# mightyFan.net
KiCad netlist of a schematic drawn in Altium Designer
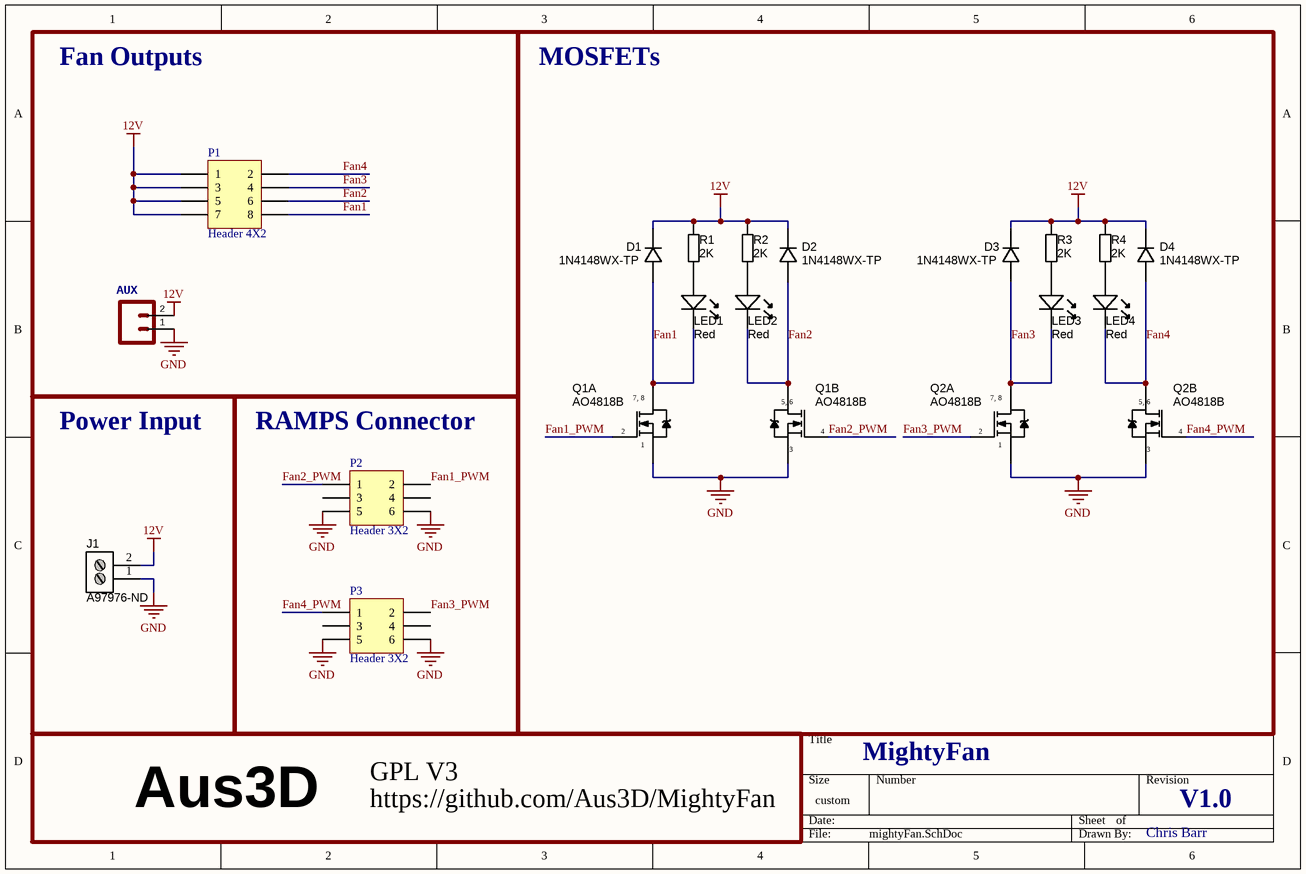
[diagram p0: mightyFan.SchDoc]

(export (version "E")
  (design (tool "Eeschema 10.0.6"))
  (components
    (comp (ref "AUX")
      (value "Standard 2-pin 0.1\" header. Use with  - straight break away headers ( PRT-00116) - right angle break away headers (PRT-00553) - swiss pins (PRT-00743) - machine pins (PRT-00117) - female headers (PRT-00115)   Molex polarized connector foot print use with: PRT-08233 with associated crimp pins and housings.  2.54_SCREWTERM for use with  PRT-10571.  3.5mm Screw Terminal footprints for  PRT-08084  5mm Screw Terminal footprints for use with PRT-08432")
      (footprint "1X02")
      (libsource (lib "SparkFun-Connectors") (part "M02PTH"))
    )
    (comp (ref "D1")
      (value "DIODE_75V_500mW")
      (footprint "SOD323")
      (description "Diode SMD 300mA 0.5W SOD323")
      (fields
        (field (name "MANUFACTURER") "Micro Commercial Co")
        (field (name "MANUFACTURER PART NUMBER") "1N4148WX-TP")
      )
      (libsource (lib "PBL - Diodes") (part "DIODE_75V_500mW"))
    )
    (comp (ref "D2")
      (value "DIODE_75V_500mW")
      (footprint "SOD323")
      (description "Diode SMD 300mA 0.5W SOD323")
      (fields
        (field (name "MANUFACTURER") "Micro Commercial Co")
        (field (name "MANUFACTURER PART NUMBER") "1N4148WX-TP")
      )
      (libsource (lib "PBL - Diodes") (part "DIODE_75V_500mW"))
    )
    (comp (ref "D3")
      (value "DIODE_75V_500mW")
      (footprint "SOD323")
      (description "Diode SMD 300mA 0.5W SOD323")
      (fields
        (field (name "MANUFACTURER") "Micro Commercial Co")
        (field (name "MANUFACTURER PART NUMBER") "1N4148WX-TP")
      )
      (libsource (lib "PBL - Diodes") (part "DIODE_75V_500mW"))
    )
    (comp (ref "D4")
      (value "DIODE_75V_500mW")
      (footprint "SOD323")
      (description "Diode SMD 300mA 0.5W SOD323")
      (fields
        (field (name "MANUFACTURER") "Micro Commercial Co")
        (field (name "MANUFACTURER PART NUMBER") "1N4148WX-TP")
      )
      (libsource (lib "PBL - Diodes") (part "DIODE_75V_500mW"))
    )
    (comp (ref "J1")
      (value "Stackable ScrewTerm")
      (footprint "2P_PCB_ScrewTerm_90S_3.81MM")
      (description "Terminal Block Screw Type THT 2-Position 3.81mm pitch")
      (fields (field (name "SUPPLIER PART NUMBER 1") "A97976-ND"))
      (libsource (lib "PBL - Connectors") (part "2P_ScrewTerm_90S_3.81MM"))
    )
    (comp (ref "LED1")
      (value "Red")
      (footprint "LED-0603-RED")
      (description "LED 0603 SMD Hyper Red 630nm 220mcd 20mA")
      (libsource (lib "PBL - Light Sources") (part "LED_SMD_Red_0603_220mcd"))
    )
    (comp (ref "LED2")
      (value "Red")
      (footprint "LED-0603-RED")
      (description "LED 0603 SMD Hyper Red 630nm 220mcd 20mA")
      (libsource (lib "PBL - Light Sources") (part "LED_SMD_Red_0603_220mcd"))
    )
    (comp (ref "LED3")
      (value "Red")
      (footprint "LED-0603-RED")
      (description "LED 0603 SMD Hyper Red 630nm 220mcd 20mA")
      (libsource (lib "PBL - Light Sources") (part "LED_SMD_Red_0603_220mcd"))
    )
    (comp (ref "LED4")
      (value "Red")
      (footprint "LED-0603-RED")
      (description "LED 0603 SMD Hyper Red 630nm 220mcd 20mA")
      (libsource (lib "PBL - Light Sources") (part "LED_SMD_Red_0603_220mcd"))
    )
    (comp (ref "P1")
      (value "Header 4X2")
      (footprint "2X4")
      (description "Header, 4-Pin, Dual row")
      (fields (field (name "PUBLISHER") "Altium Limited"))
      (libsource (lib "Miscellaneous Connectors") (part "Header 4X2"))
    )
    (comp (ref "P2")
      (value "Header 3X2")
      (footprint "Header-3x2-female")
      (description "Header, 3-Pin, Dual row")
      (fields (field (name "PUBLISHER") "Altium Limited"))
      (libsource (lib "Miscellaneous Connectors") (part "Header 3X2"))
    )
    (comp (ref "P3")
      (value "Header 3X2")
      (footprint "Header-3x2-female")
      (description "Header, 3-Pin, Dual row")
      (fields (field (name "PUBLISHER") "Altium Limited"))
      (libsource (lib "Miscellaneous Connectors") (part "Header 3X2"))
    )
    (comp (ref "Q1")
      (value "MOSFET_AO4818B")
      (footprint "SOIC127P600X175-8AN")
      (description "MOSFET Dual-Channel 30V 8.5A SOIC-8 SMD")
      (fields (field (name "MANUFACTURER PART NUMBER 1") "AO4818B"))
      (libsource (lib "PBL - Transistors") (part "MOSFET_AO4818B"))
    )
    (comp (ref "Q2")
      (value "MOSFET_AO4818B")
      (footprint "SOIC127P600X175-8AN")
      (description "MOSFET Dual-Channel 30V 8.5A SOIC-8 SMD")
      (fields (field (name "MANUFACTURER PART NUMBER 1") "AO4818B"))
      (libsource (lib "PBL - Transistors") (part "MOSFET_AO4818B"))
    )
    (comp (ref "R1")
      (value "2K")
      (footprint "RESC1608X55N")
      (description "Resistor SMD chip 330 Ohm 0.1W 5% 0603")
      (fields (field (name "TOLERANCE") "±5%") (field (name "Comment") "Thick Film"))
      (libsource (lib "PBL - Resistors") (part "RES_330R_0603_5%"))
    )
    (comp (ref "R2")
      (value "2K")
      (footprint "RESC1608X55N")
      (description "Resistor SMD chip 330 Ohm 0.1W 5% 0603")
      (fields (field (name "TOLERANCE") "±5%") (field (name "Comment") "Thick Film"))
      (libsource (lib "PBL - Resistors") (part "RES_330R_0603_5%"))
    )
    (comp (ref "R3")
      (value "2K")
      (footprint "RESC1608X55N")
      (description "Resistor SMD chip 330 Ohm 0.1W 5% 0603")
      (fields (field (name "TOLERANCE") "±5%") (field (name "Comment") "Thick Film"))
      (libsource (lib "PBL - Resistors") (part "RES_330R_0603_5%"))
    )
    (comp (ref "R4")
      (value "2K")
      (footprint "RESC1608X55N")
      (description "Resistor SMD chip 330 Ohm 0.1W 5% 0603")
      (fields (field (name "TOLERANCE") "±5%") (field (name "Comment") "Thick Film"))
      (libsource (lib "PBL - Resistors") (part "RES_330R_0603_5%"))
    )
  )
  (nets
    (net (code "1") (name "/Fan1") (class "Default")
      (node (ref "D1") (pin "A") (pinfunction "A_A") (pintype "passive"))
      (node (ref "LED1") (pin "K") (pinfunction "K_K") (pintype "passive"))
      (node (ref "P1") (pin "8") (pinfunction "8_8") (pintype "passive"))
      (node (ref "Q1") (pin "7") (pinfunction "D_7") (pintype "passive"))
      (node (ref "Q1") (pin "8") (pinfunction "D_8") (pintype "passive"))
    )
    (net (code "2") (name "/Fan1_PWM") (class "Default")
      (node (ref "P2") (pin "2") (pinfunction "2_2") (pintype "passive"))
      (node (ref "Q1") (pin "2") (pinfunction "G_2") (pintype "passive"))
    )
    (net (code "3") (name "/Fan2") (class "Default")
      (node (ref "D2") (pin "A") (pinfunction "A_A") (pintype "passive"))
      (node (ref "LED2") (pin "K") (pinfunction "K_K") (pintype "passive"))
      (node (ref "P1") (pin "6") (pinfunction "6_6") (pintype "passive"))
      (node (ref "Q1") (pin "5") (pinfunction "D_5") (pintype "passive"))
      (node (ref "Q1") (pin "6") (pinfunction "D_6") (pintype "passive"))
    )
    (net (code "4") (name "/Fan2_PWM") (class "Default")
      (node (ref "P2") (pin "1") (pinfunction "1_1") (pintype "passive"))
      (node (ref "Q1") (pin "4") (pinfunction "G_4") (pintype "passive"))
    )
    (net (code "5") (name "/Fan3") (class "Default")
      (node (ref "D3") (pin "A") (pinfunction "A_A") (pintype "passive"))
      (node (ref "LED3") (pin "K") (pinfunction "K_K") (pintype "passive"))
      (node (ref "P1") (pin "4") (pinfunction "4_4") (pintype "passive"))
      (node (ref "Q2") (pin "7") (pinfunction "D_7") (pintype "passive"))
      (node (ref "Q2") (pin "8") (pinfunction "D_8") (pintype "passive"))
    )
    (net (code "6") (name "/Fan3_PWM") (class "Default")
      (node (ref "P3") (pin "2") (pinfunction "2_2") (pintype "passive"))
      (node (ref "Q2") (pin "2") (pinfunction "G_2") (pintype "passive"))
    )
    (net (code "7") (name "/Fan4") (class "Default")
      (node (ref "D4") (pin "A") (pinfunction "A_A") (pintype "passive"))
      (node (ref "LED4") (pin "K") (pinfunction "K_K") (pintype "passive"))
      (node (ref "P1") (pin "2") (pinfunction "2_2") (pintype "passive"))
      (node (ref "Q2") (pin "5") (pinfunction "D_5") (pintype "passive"))
      (node (ref "Q2") (pin "6") (pinfunction "D_6") (pintype "passive"))
    )
    (net (code "8") (name "/Fan4_PWM") (class "Default")
      (node (ref "P3") (pin "1") (pinfunction "1_1") (pintype "passive"))
      (node (ref "Q2") (pin "4") (pinfunction "G_4") (pintype "passive"))
    )
    (net (code "9") (name "12V") (class "Default")
      (node (ref "AUX") (pin "2") (pinfunction "2_2") (pintype "passive"))
      (node (ref "D1") (pin "K") (pinfunction "K_K") (pintype "passive"))
      (node (ref "D2") (pin "K") (pinfunction "K_K") (pintype "passive"))
      (node (ref "D3") (pin "K") (pinfunction "K_K") (pintype "passive"))
      (node (ref "D4") (pin "K") (pinfunction "K_K") (pintype "passive"))
      (node (ref "J1") (pin "2") (pinfunction "2_2") (pintype "passive"))
      (node (ref "P1") (pin "1") (pinfunction "1_1") (pintype "passive"))
      (node (ref "P1") (pin "3") (pinfunction "3_3") (pintype "passive"))
      (node (ref "P1") (pin "5") (pinfunction "5_5") (pintype "passive"))
      (node (ref "P1") (pin "7") (pinfunction "7_7") (pintype "passive"))
      (node (ref "R1") (pin "1") (pinfunction "1_1") (pintype "passive"))
      (node (ref "R2") (pin "1") (pinfunction "1_1") (pintype "passive"))
      (node (ref "R3") (pin "1") (pinfunction "1_1") (pintype "passive"))
      (node (ref "R4") (pin "1") (pinfunction "1_1") (pintype "passive"))
    )
    (net (code "10") (name "GND") (class "Default")
      (node (ref "AUX") (pin "1") (pinfunction "1_1") (pintype "passive"))
      (node (ref "J1") (pin "1") (pinfunction "1_1") (pintype "passive"))
      (node (ref "P2") (pin "5") (pinfunction "5_5") (pintype "passive"))
      (node (ref "P2") (pin "6") (pinfunction "6_6") (pintype "passive"))
      (node (ref "P3") (pin "5") (pinfunction "5_5") (pintype "passive"))
      (node (ref "P3") (pin "6") (pinfunction "6_6") (pintype "passive"))
      (node (ref "Q1") (pin "1") (pinfunction "S_1") (pintype "passive"))
      (node (ref "Q1") (pin "3") (pinfunction "S_3") (pintype "passive"))
      (node (ref "Q2") (pin "1") (pinfunction "S_1") (pintype "passive"))
      (node (ref "Q2") (pin "3") (pinfunction "S_3") (pintype "passive"))
    )
    (net (code "11") (name "Net-(LED1-PadA)") (class "Default")
      (node (ref "LED1") (pin "A") (pinfunction "A_A") (pintype "passive"))
      (node (ref "R1") (pin "2") (pinfunction "2_2") (pintype "passive"))
    )
    (net (code "12") (name "Net-(LED2-PadA)") (class "Default")
      (node (ref "LED2") (pin "A") (pinfunction "A_A") (pintype "passive"))
      (node (ref "R2") (pin "2") (pinfunction "2_2") (pintype "passive"))
    )
    (net (code "13") (name "Net-(LED3-PadA)") (class "Default")
      (node (ref "LED3") (pin "A") (pinfunction "A_A") (pintype "passive"))
      (node (ref "R3") (pin "2") (pinfunction "2_2") (pintype "passive"))
    )
    (net (code "14") (name "Net-(LED4-PadA)") (class "Default")
      (node (ref "LED4") (pin "A") (pinfunction "A_A") (pintype "passive"))
      (node (ref "R4") (pin "2") (pinfunction "2_2") (pintype "passive"))
    )
    (net (code "15") (name "unconnected-(P2-Pad3)") (class "Default")
      (node (ref "P2") (pin "3") (pinfunction "3_3") (pintype "passive"))
    )
    (net (code "16") (name "unconnected-(P2-Pad4)") (class "Default")
      (node (ref "P2") (pin "4") (pinfunction "4_4") (pintype "passive"))
    )
    (net (code "17") (name "unconnected-(P3-Pad3)") (class "Default")
      (node (ref "P3") (pin "3") (pinfunction "3_3") (pintype "passive"))
    )
    (net (code "18") (name "unconnected-(P3-Pad4)") (class "Default")
      (node (ref "P3") (pin "4") (pinfunction "4_4") (pintype "passive"))
    )
  )
)
